# 408HR_pcbminions.net
KiCad netlist of a schematic drawn in Altium Designer
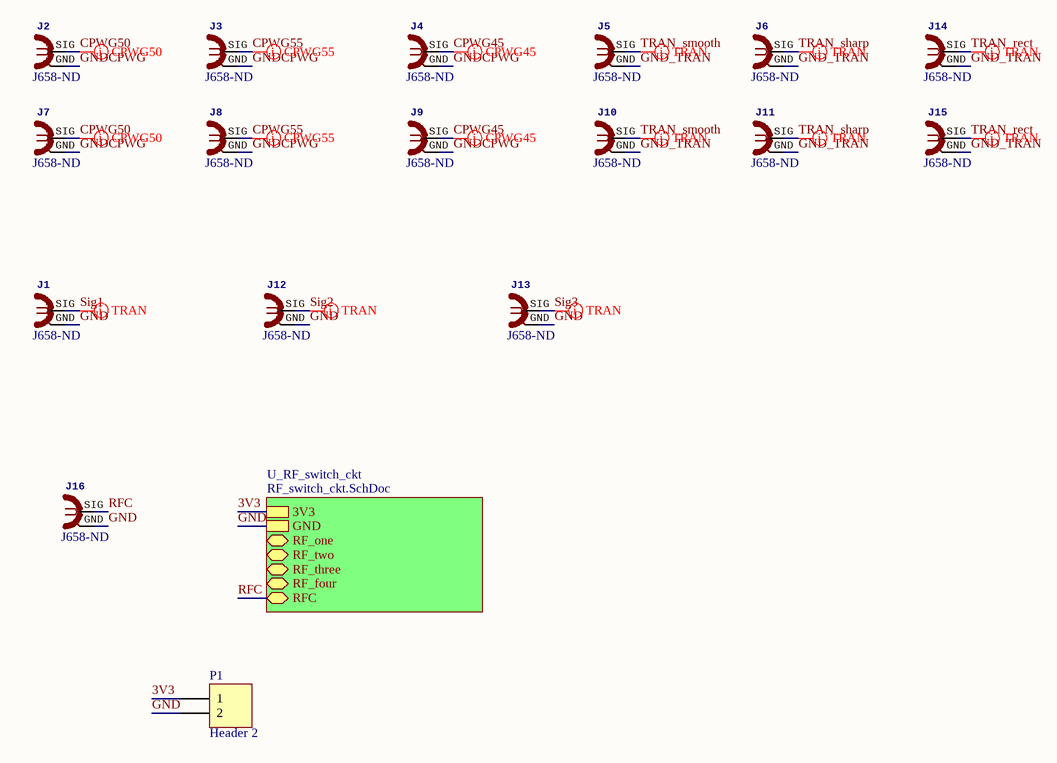
[diagram p0: 408HR_pcbminions.SchDoc]

(export (version "E")
  (design (tool "Eeschema 10.0.6"))
  (components
    (comp (ref "J1")
      (value "SMA 50 Ohm edge")
      (footprint "SMA-OSHPARK-4L-1.6MM- ALT3")
      (fields
        (field (name "SUPPLIER PART NUMBER 1") "J658-ND")
        (field (name "LIBRARYNAME") "dword1511-connectors")
      )
      (libsource (lib "wcsng_altium") (part "SMA-OSHPARK-4L-1.6MM-ALT3"))
    )
    (comp (ref "J2")
      (value "SMA 50 Ohm edge")
      (footprint "SMA-OSHPARK-4L-1.6MM- ALT3")
      (fields
        (field (name "SUPPLIER PART NUMBER 1") "J658-ND")
        (field (name "LIBRARYNAME") "dword1511-connectors")
      )
      (libsource (lib "wcsng_altium") (part "SMA-OSHPARK-4L-1.6MM-ALT3"))
    )
    (comp (ref "J3")
      (value "SMA 50 Ohm edge")
      (footprint "SMA-OSHPARK-4L-1.6MM- ALT3")
      (fields
        (field (name "SUPPLIER PART NUMBER 1") "J658-ND")
        (field (name "LIBRARYNAME") "dword1511-connectors")
      )
      (libsource (lib "wcsng_altium") (part "SMA-OSHPARK-4L-1.6MM-ALT3"))
    )
    (comp (ref "J4")
      (value "SMA 50 Ohm edge")
      (footprint "SMA-OSHPARK-4L-1.6MM- ALT3")
      (fields
        (field (name "SUPPLIER PART NUMBER 1") "J658-ND")
        (field (name "LIBRARYNAME") "dword1511-connectors")
      )
      (libsource (lib "wcsng_altium") (part "SMA-OSHPARK-4L-1.6MM-ALT3"))
    )
    (comp (ref "J5")
      (value "SMA 50 Ohm edge")
      (footprint "SMA-OSHPARK-4L-1.6MM- ALT3")
      (fields
        (field (name "SUPPLIER PART NUMBER 1") "J658-ND")
        (field (name "LIBRARYNAME") "dword1511-connectors")
      )
      (libsource (lib "wcsng_altium") (part "SMA-OSHPARK-4L-1.6MM-ALT3"))
    )
    (comp (ref "J6")
      (value "SMA 50 Ohm edge")
      (footprint "SMA-OSHPARK-4L-1.6MM- ALT3")
      (fields
        (field (name "SUPPLIER PART NUMBER 1") "J658-ND")
        (field (name "LIBRARYNAME") "dword1511-connectors")
      )
      (libsource (lib "wcsng_altium") (part "SMA-OSHPARK-4L-1.6MM-ALT3"))
    )
    (comp (ref "J7")
      (value "SMA 50 Ohm edge")
      (footprint "SMA-OSHPARK-4L-1.6MM- ALT3")
      (fields
        (field (name "SUPPLIER PART NUMBER 1") "J658-ND")
        (field (name "LIBRARYNAME") "dword1511-connectors")
      )
      (libsource (lib "wcsng_altium") (part "SMA-OSHPARK-4L-1.6MM-ALT3"))
    )
    (comp (ref "J8")
      (value "SMA 50 Ohm edge")
      (footprint "SMA-OSHPARK-4L-1.6MM- ALT3")
      (fields
        (field (name "SUPPLIER PART NUMBER 1") "J658-ND")
        (field (name "LIBRARYNAME") "dword1511-connectors")
      )
      (libsource (lib "wcsng_altium") (part "SMA-OSHPARK-4L-1.6MM-ALT3"))
    )
    (comp (ref "J9")
      (value "SMA 50 Ohm edge")
      (footprint "SMA-OSHPARK-4L-1.6MM- ALT3")
      (fields
        (field (name "SUPPLIER PART NUMBER 1") "J658-ND")
        (field (name "LIBRARYNAME") "dword1511-connectors")
      )
      (libsource (lib "wcsng_altium") (part "SMA-OSHPARK-4L-1.6MM-ALT3"))
    )
    (comp (ref "J10")
      (value "SMA 50 Ohm edge")
      (footprint "SMA-OSHPARK-4L-1.6MM- ALT3")
      (fields
        (field (name "SUPPLIER PART NUMBER 1") "J658-ND")
        (field (name "LIBRARYNAME") "dword1511-connectors")
      )
      (libsource (lib "wcsng_altium") (part "SMA-OSHPARK-4L-1.6MM-ALT3"))
    )
    (comp (ref "J11")
      (value "SMA 50 Ohm edge")
      (footprint "SMA-OSHPARK-4L-1.6MM- ALT3")
      (fields
        (field (name "SUPPLIER PART NUMBER 1") "J658-ND")
        (field (name "LIBRARYNAME") "dword1511-connectors")
      )
      (libsource (lib "wcsng_altium") (part "SMA-OSHPARK-4L-1.6MM-ALT3"))
    )
    (comp (ref "J12")
      (value "SMA 50 Ohm edge")
      (footprint "SMA-OSHPARK-4L-1.6MM- ALT3")
      (fields
        (field (name "SUPPLIER PART NUMBER 1") "J658-ND")
        (field (name "LIBRARYNAME") "dword1511-connectors")
      )
      (libsource (lib "wcsng_altium") (part "SMA-OSHPARK-4L-1.6MM-ALT3"))
    )
    (comp (ref "J13")
      (value "SMA 50 Ohm edge")
      (footprint "SMA-OSHPARK-4L-1.6MM- ALT3")
      (fields
        (field (name "SUPPLIER PART NUMBER 1") "J658-ND")
        (field (name "LIBRARYNAME") "dword1511-connectors")
      )
      (libsource (lib "wcsng_altium") (part "SMA-OSHPARK-4L-1.6MM-ALT3"))
    )
    (comp (ref "J14")
      (value "SMA 50 Ohm edge")
      (footprint "SMA-OSHPARK-4L-1.6MM- ALT3")
      (fields
        (field (name "SUPPLIER PART NUMBER 1") "J658-ND")
        (field (name "LIBRARYNAME") "dword1511-connectors")
      )
      (libsource (lib "wcsng_altium") (part "SMA-OSHPARK-4L-1.6MM-ALT3"))
    )
    (comp (ref "J15")
      (value "SMA 50 Ohm edge")
      (footprint "SMA-OSHPARK-4L-1.6MM- ALT3")
      (fields
        (field (name "SUPPLIER PART NUMBER 1") "J658-ND")
        (field (name "LIBRARYNAME") "dword1511-connectors")
      )
      (libsource (lib "wcsng_altium") (part "SMA-OSHPARK-4L-1.6MM-ALT3"))
    )
    (comp (ref "J16")
      (value "SMA 50 Ohm edge")
      (footprint "SMA-OSHPARK-4L-1.6MM- ALT3")
      (fields
        (field (name "SUPPLIER PART NUMBER 1") "J658-ND")
        (field (name "LIBRARYNAME") "dword1511-connectors")
      )
      (libsource (lib "wcsng_altium") (part "SMA-OSHPARK-4L-1.6MM-ALT3"))
    )
    (comp (ref "P1")
      (value "Header 2")
      (footprint "HDR1X2")
      (description "Header, 2-Pin")
      (fields (field (name "PUBLISHER") "Altium Limited"))
      (libsource (lib "Miscellaneous Connectors") (part "Header 2"))
    )
  )
  (nets
    (net (code "1") (name "/3V3") (class "Default")
      (node (ref "P1") (pin "1") (pinfunction "1_1") (pintype "passive"))
    )
    (net (code "2") (name "/CPWG45") (class "Default")
      (node (ref "J4") (pin "SIG") (pinfunction "SIG_SIG") (pintype "passive"))
      (node (ref "J9") (pin "SIG") (pinfunction "SIG_SIG") (pintype "passive"))
    )
    (net (code "3") (name "/CPWG50") (class "Default")
      (node (ref "J2") (pin "SIG") (pinfunction "SIG_SIG") (pintype "passive"))
      (node (ref "J7") (pin "SIG") (pinfunction "SIG_SIG") (pintype "passive"))
    )
    (net (code "4") (name "/CPWG55") (class "Default")
      (node (ref "J3") (pin "SIG") (pinfunction "SIG_SIG") (pintype "passive"))
      (node (ref "J8") (pin "SIG") (pinfunction "SIG_SIG") (pintype "passive"))
    )
    (net (code "5") (name "/GND") (class "Default")
      (node (ref "J1") (pin "GND") (pinfunction "GND_GND") (pintype "passive"))
      (node (ref "J12") (pin "GND") (pinfunction "GND_GND") (pintype "passive"))
      (node (ref "J13") (pin "GND") (pinfunction "GND_GND") (pintype "passive"))
      (node (ref "J16") (pin "GND") (pinfunction "GND_GND") (pintype "passive"))
      (node (ref "P1") (pin "2") (pinfunction "2_2") (pintype "passive"))
    )
    (net (code "6") (name "/GNDCPWG") (class "Default")
      (node (ref "J2") (pin "GND") (pinfunction "GND_GND") (pintype "passive"))
      (node (ref "J3") (pin "GND") (pinfunction "GND_GND") (pintype "passive"))
      (node (ref "J4") (pin "GND") (pinfunction "GND_GND") (pintype "passive"))
      (node (ref "J7") (pin "GND") (pinfunction "GND_GND") (pintype "passive"))
      (node (ref "J8") (pin "GND") (pinfunction "GND_GND") (pintype "passive"))
      (node (ref "J9") (pin "GND") (pinfunction "GND_GND") (pintype "passive"))
    )
    (net (code "7") (name "/GND_TRAN") (class "Default")
      (node (ref "J10") (pin "GND") (pinfunction "GND_GND") (pintype "passive"))
      (node (ref "J11") (pin "GND") (pinfunction "GND_GND") (pintype "passive"))
      (node (ref "J14") (pin "GND") (pinfunction "GND_GND") (pintype "passive"))
      (node (ref "J15") (pin "GND") (pinfunction "GND_GND") (pintype "passive"))
      (node (ref "J5") (pin "GND") (pinfunction "GND_GND") (pintype "passive"))
      (node (ref "J6") (pin "GND") (pinfunction "GND_GND") (pintype "passive"))
    )
    (net (code "8") (name "/RFC") (class "Default")
      (node (ref "J16") (pin "SIG") (pinfunction "SIG_SIG") (pintype "passive"))
    )
    (net (code "13") (name "/Sig1") (class "Default")
      (node (ref "J1") (pin "SIG") (pinfunction "SIG_SIG") (pintype "passive"))
    )
    (net (code "14") (name "/Sig2") (class "Default")
      (node (ref "J12") (pin "SIG") (pinfunction "SIG_SIG") (pintype "passive"))
    )
    (net (code "15") (name "/Sig3") (class "Default")
      (node (ref "J13") (pin "SIG") (pinfunction "SIG_SIG") (pintype "passive"))
    )
    (net (code "16") (name "/TRAN_rect") (class "Default")
      (node (ref "J14") (pin "SIG") (pinfunction "SIG_SIG") (pintype "passive"))
      (node (ref "J15") (pin "SIG") (pinfunction "SIG_SIG") (pintype "passive"))
    )
    (net (code "17") (name "/TRAN_sharp") (class "Default")
      (node (ref "J11") (pin "SIG") (pinfunction "SIG_SIG") (pintype "passive"))
      (node (ref "J6") (pin "SIG") (pinfunction "SIG_SIG") (pintype "passive"))
    )
    (net (code "18") (name "/TRAN_smooth") (class "Default")
      (node (ref "J10") (pin "SIG") (pinfunction "SIG_SIG") (pintype "passive"))
      (node (ref "J5") (pin "SIG") (pinfunction "SIG_SIG") (pintype "passive"))
    )
  )
)
